# esp3212_breakout_v1.net
KiCad netlist of a schematic drawn in EAGLE
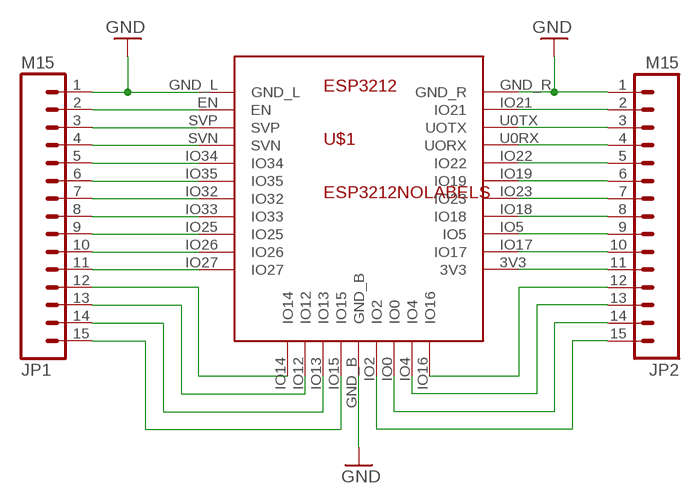
[diagram p0: schematic, sheet 1]

(export (version "E")
  (design (tool "Eeschema 10.0.6"))
  (components
    (comp (ref "JP1")
      (value "M15")
      (footprint "eagle-import:1X15")
      (libsource (lib "eagle-import") (part "M15"))
    )
    (comp (ref "JP2")
      (value "M15")
      (footprint "eagle-import:1X15")
      (libsource (lib "eagle-import") (part "M15"))
    )
    (comp (ref "U$1")
      (value "ESP3212NOLABELS")
      (footprint "eagle-import:ESP3212_NOPINLABELS")
      (libsource (lib "eagle-import") (part "ESP3212NOLABELS"))
    )
  )
  (nets
    (net (code "1") (name "GND") (class "Default")
      (node (ref "JP1") (pin "1") (pinfunction "1_1") (pintype "passive"))
      (node (ref "JP2") (pin "1") (pinfunction "1_1") (pintype "passive"))
      (node (ref "U$1") (pin "GND_B") (pinfunction "GND_B_GND_B") (pintype "bidirectional"))
      (node (ref "U$1") (pin "GND_L") (pinfunction "GND_L_GND_L") (pintype "bidirectional"))
      (node (ref "U$1") (pin "GND_R") (pinfunction "GND_R_GND_R") (pintype "bidirectional"))
    )
    (net (code "2") (name "Net-(JP1-Pad2)") (class "Default")
      (node (ref "JP1") (pin "2") (pinfunction "2_2") (pintype "passive"))
      (node (ref "U$1") (pin "EN") (pinfunction "EN_EN") (pintype "bidirectional"))
    )
    (net (code "3") (name "Net-(JP1-Pad3)") (class "Default")
      (node (ref "JP1") (pin "3") (pinfunction "3_3") (pintype "passive"))
      (node (ref "U$1") (pin "SVP") (pinfunction "SVP_SVP") (pintype "bidirectional"))
    )
    (net (code "4") (name "Net-(JP1-Pad4)") (class "Default")
      (node (ref "JP1") (pin "4") (pinfunction "4_4") (pintype "passive"))
      (node (ref "U$1") (pin "SVN") (pinfunction "SVN_SVN") (pintype "bidirectional"))
    )
    (net (code "5") (name "Net-(JP1-Pad5)") (class "Default")
      (node (ref "JP1") (pin "5") (pinfunction "5_5") (pintype "passive"))
      (node (ref "U$1") (pin "IO34") (pinfunction "IO34_IO34") (pintype "bidirectional"))
    )
    (net (code "6") (name "Net-(JP1-Pad6)") (class "Default")
      (node (ref "JP1") (pin "6") (pinfunction "6_6") (pintype "passive"))
      (node (ref "U$1") (pin "IO35") (pinfunction "IO35_IO35") (pintype "bidirectional"))
    )
    (net (code "7") (name "Net-(JP1-Pad7)") (class "Default")
      (node (ref "JP1") (pin "7") (pinfunction "7_7") (pintype "passive"))
      (node (ref "U$1") (pin "IO32") (pinfunction "IO32_IO32") (pintype "bidirectional"))
    )
    (net (code "8") (name "Net-(JP1-Pad8)") (class "Default")
      (node (ref "JP1") (pin "8") (pinfunction "8_8") (pintype "passive"))
      (node (ref "U$1") (pin "IO33") (pinfunction "IO33_IO33") (pintype "bidirectional"))
    )
    (net (code "9") (name "Net-(JP1-Pad9)") (class "Default")
      (node (ref "JP1") (pin "9") (pinfunction "9_9") (pintype "passive"))
      (node (ref "U$1") (pin "IO25") (pinfunction "IO25_IO25") (pintype "bidirectional"))
    )
    (net (code "10") (name "Net-(JP1-Pad10)") (class "Default")
      (node (ref "JP1") (pin "10") (pinfunction "10_10") (pintype "passive"))
      (node (ref "U$1") (pin "IO26") (pinfunction "IO26_IO26") (pintype "bidirectional"))
    )
    (net (code "11") (name "Net-(JP1-Pad11)") (class "Default")
      (node (ref "JP1") (pin "11") (pinfunction "11_11") (pintype "passive"))
      (node (ref "U$1") (pin "IO27") (pinfunction "IO27_IO27") (pintype "bidirectional"))
    )
    (net (code "12") (name "Net-(JP1-Pad12)") (class "Default")
      (node (ref "JP1") (pin "12") (pinfunction "12_12") (pintype "passive"))
      (node (ref "U$1") (pin "IO14") (pinfunction "IO14_IO14") (pintype "bidirectional"))
    )
    (net (code "13") (name "Net-(JP1-Pad13)") (class "Default")
      (node (ref "JP1") (pin "13") (pinfunction "13_13") (pintype "passive"))
      (node (ref "U$1") (pin "IO12") (pinfunction "IO12_IO12") (pintype "bidirectional"))
    )
    (net (code "14") (name "Net-(JP1-Pad14)") (class "Default")
      (node (ref "JP1") (pin "14") (pinfunction "14_14") (pintype "passive"))
      (node (ref "U$1") (pin "IO13") (pinfunction "IO13_IO13") (pintype "bidirectional"))
    )
    (net (code "15") (name "Net-(JP1-Pad15)") (class "Default")
      (node (ref "JP1") (pin "15") (pinfunction "15_15") (pintype "passive"))
      (node (ref "U$1") (pin "IO15") (pinfunction "IO15_IO15") (pintype "bidirectional"))
    )
    (net (code "16") (name "Net-(JP2-Pad2)") (class "Default")
      (node (ref "JP2") (pin "2") (pinfunction "2_2") (pintype "passive"))
      (node (ref "U$1") (pin "IO21") (pinfunction "IO21_IO21") (pintype "bidirectional"))
    )
    (net (code "17") (name "Net-(JP2-Pad5)") (class "Default")
      (node (ref "JP2") (pin "5") (pinfunction "5_5") (pintype "passive"))
      (node (ref "U$1") (pin "IO22") (pinfunction "IO22_IO22") (pintype "bidirectional"))
    )
    (net (code "18") (name "Net-(JP2-Pad6)") (class "Default")
      (node (ref "JP2") (pin "6") (pinfunction "6_6") (pintype "passive"))
      (node (ref "U$1") (pin "IO19") (pinfunction "IO19_IO19") (pintype "bidirectional"))
    )
    (net (code "19") (name "Net-(JP2-Pad7)") (class "Default")
      (node (ref "JP2") (pin "7") (pinfunction "7_7") (pintype "passive"))
      (node (ref "U$1") (pin "IO23") (pinfunction "IO23_IO23") (pintype "bidirectional"))
    )
    (net (code "20") (name "Net-(JP2-Pad8)") (class "Default")
      (node (ref "JP2") (pin "8") (pinfunction "8_8") (pintype "passive"))
      (node (ref "U$1") (pin "IO18") (pinfunction "IO18_IO18") (pintype "bidirectional"))
    )
    (net (code "21") (name "Net-(JP2-Pad9)") (class "Default")
      (node (ref "JP2") (pin "9") (pinfunction "9_9") (pintype "passive"))
      (node (ref "U$1") (pin "IO5") (pinfunction "IO5_IO5") (pintype "bidirectional"))
    )
    (net (code "22") (name "Net-(JP2-Pad10)") (class "Default")
      (node (ref "JP2") (pin "10") (pinfunction "10_10") (pintype "passive"))
      (node (ref "U$1") (pin "IO17") (pinfunction "IO17_IO17") (pintype "bidirectional"))
    )
    (net (code "23") (name "Net-(JP2-Pad11)") (class "Default")
      (node (ref "JP2") (pin "11") (pinfunction "11_11") (pintype "passive"))
      (node (ref "U$1") (pin "3V3") (pinfunction "3V3_3V3") (pintype "bidirectional"))
    )
    (net (code "24") (name "Net-(JP2-Pad12)") (class "Default")
      (node (ref "JP2") (pin "12") (pinfunction "12_12") (pintype "passive"))
      (node (ref "U$1") (pin "IO16") (pinfunction "IO16_IO16") (pintype "bidirectional"))
    )
    (net (code "25") (name "Net-(JP2-Pad13)") (class "Default")
      (node (ref "JP2") (pin "13") (pinfunction "13_13") (pintype "passive"))
      (node (ref "U$1") (pin "IO4") (pinfunction "IO4_IO4") (pintype "bidirectional"))
    )
    (net (code "26") (name "Net-(JP2-Pad14)") (class "Default")
      (node (ref "JP2") (pin "14") (pinfunction "14_14") (pintype "passive"))
      (node (ref "U$1") (pin "IO0") (pinfunction "IO0_IO0") (pintype "bidirectional"))
    )
    (net (code "27") (name "Net-(JP2-Pad15)") (class "Default")
      (node (ref "JP2") (pin "15") (pinfunction "15_15") (pintype "passive"))
      (node (ref "U$1") (pin "IO2") (pinfunction "IO2_IO2") (pintype "bidirectional"))
    )
    (net (code "28") (name "Net-(U$1-UORX)") (class "Default")
      (node (ref "JP2") (pin "4") (pinfunction "4_4") (pintype "passive"))
      (node (ref "U$1") (pin "U0RX") (pinfunction "UORX_U0RX") (pintype "bidirectional"))
    )
    (net (code "29") (name "Net-(U$1-UOTX)") (class "Default")
      (node (ref "JP2") (pin "3") (pinfunction "3_3") (pintype "passive"))
      (node (ref "U$1") (pin "U0TX") (pinfunction "UOTX_U0TX") (pintype "bidirectional"))
    )
  )
)
